# Alimentations.net
KiCad netlist of a schematic drawn in Altium Designer
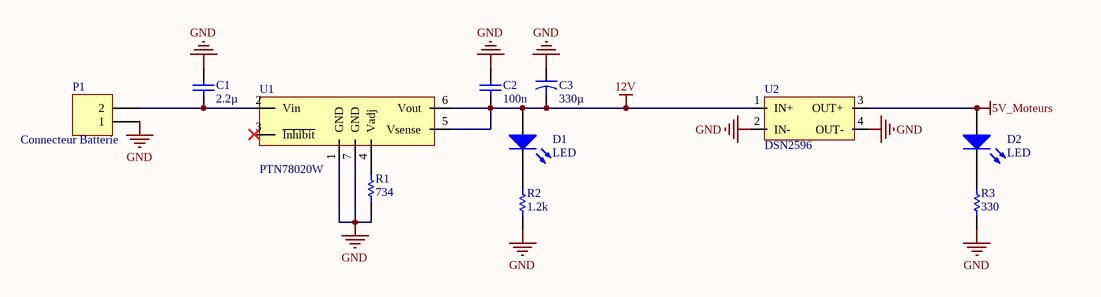
[diagram p0: Alimentations.SchDoc]

(export (version "E")
  (design (tool "Eeschema 10.0.6"))
  (components
    (comp (ref "C1")
      (value "2.2µ")
      (footprint "RAD-0.3")
      (fields (field (name "Comment") "Cap") (field (name "PUBLISHER") "Altium Limited"))
      (libsource (lib "Miscellaneous Devices") (part "Cap"))
    )
    (comp (ref "C2")
      (value "100n")
      (footprint "RAD-0.3")
      (fields (field (name "Comment") "Cap") (field (name "PUBLISHER") "Altium Limited"))
      (libsource (lib "Miscellaneous Devices") (part "Cap"))
    )
    (comp (ref "C3")
      (value "330µ")
      (footprint "CAPR5-4X5")
      (fields (field (name "Comment") "Cap2") (field (name "PUBLISHER") "Altium Limited"))
      (libsource (lib "Miscellaneous Devices") (part "Cap2"))
    )
    (comp (ref "D1")
      (value "LED")
      (footprint "C0805")
      (description "LED Bleu")
      (fields (field (name "PUBLISHER") "Altium Limited"))
      (libsource (lib "Miscellaneous Devices") (part "LED1"))
    )
    (comp (ref "D2")
      (value "LED")
      (footprint "C0805")
      (description "LED Verte")
      (fields (field (name "PUBLISHER") "Altium Limited"))
      (libsource (lib "Miscellaneous Devices") (part "LED1"))
    )
    (comp (ref "P1")
      (value "Connecteur Batterie")
      (footprint "HDR1X2")
      (description "Header, 2-Pin")
      (fields (field (name "PUBLISHER") "Altium Limited"))
      (libsource (lib "Miscellaneous Connectors") (part "Header 2"))
    )
    (comp (ref "R1")
      (value "734")
      (footprint "AXIAL-0.3")
      (description "734R 1%")
      (fields (field (name "Comment") "Res1") (field (name "PUBLISHER") "Altium Limited"))
      (libsource (lib "Miscellaneous Devices") (part "Res1"))
    )
    (comp (ref "R2")
      (value "1.2k")
      (footprint "AXIAL-0.3")
      (fields (field (name "Comment") "Res1") (field (name "PUBLISHER") "Altium Limited"))
      (libsource (lib "Miscellaneous Devices") (part "Res1"))
    )
    (comp (ref "R3")
      (value "330")
      (footprint "AXIAL-0.3")
      (description "330R")
      (fields (field (name "Comment") "Res1") (field (name "PUBLISHER") "Altium Limited"))
      (libsource (lib "Miscellaneous Devices") (part "Res1"))
    )
    (comp (ref "U1")
      (value "PTN78020W")
      (description "Alim à découpage 6A")
      (libsource (lib "lib_Gabriel") (part "PTN78020W"))
    )
    (comp (ref "U2")
      (value "DSN2596")
      (description "Module Buck 24V 12V 5V - 3A")
      (libsource (lib "lib_Gabriel") (part "DSN2596"))
    )
  )
  (nets
    (net (code "1") (name "5V_Moteurs") (class "Default")
      (node (ref "D2") (pin "1") (pinfunction "A_1") (pintype "passive"))
      (node (ref "U2") (pin "3") (pinfunction "OUT+_3") (pintype "passive"))
    )
    (net (code "2") (name "12V") (class "Default")
      (node (ref "C2") (pin "1") (pinfunction "1_1") (pintype "passive"))
      (node (ref "C3") (pin "2") (pinfunction "2_2") (pintype "passive"))
      (node (ref "D1") (pin "1") (pinfunction "A_1") (pintype "passive"))
      (node (ref "U1") (pin "5") (pinfunction "Vsense_5") (pintype "passive"))
      (node (ref "U1") (pin "6") (pinfunction "Vout_6") (pintype "passive"))
      (node (ref "U2") (pin "1") (pinfunction "IN+_1") (pintype "passive"))
    )
    (net (code "3") (name "GND") (class "Default")
      (node (ref "C1") (pin "2") (pinfunction "2_2") (pintype "passive"))
      (node (ref "C2") (pin "2") (pinfunction "2_2") (pintype "passive"))
      (node (ref "C3") (pin "1") (pinfunction "1_1") (pintype "passive"))
      (node (ref "P1") (pin "1") (pinfunction "1_1") (pintype "passive"))
      (node (ref "R1") (pin "1") (pinfunction "1_1") (pintype "passive"))
      (node (ref "R2") (pin "2") (pinfunction "2_2") (pintype "passive"))
      (node (ref "R3") (pin "2") (pinfunction "2_2") (pintype "passive"))
      (node (ref "U1") (pin "1") (pinfunction "GND_1") (pintype "passive"))
      (node (ref "U1") (pin "7") (pinfunction "GND_7") (pintype "passive"))
      (node (ref "U2") (pin "2") (pinfunction "IN-_2") (pintype "passive"))
      (node (ref "U2") (pin "4") (pinfunction "OUT-_4") (pintype "passive"))
    )
    (net (code "4") (name "Net-(D1-K)") (class "Default")
      (node (ref "D1") (pin "2") (pinfunction "K_2") (pintype "passive"))
      (node (ref "R2") (pin "1") (pinfunction "1_1") (pintype "passive"))
    )
    (net (code "5") (name "Net-(D2-K)") (class "Default")
      (node (ref "D2") (pin "2") (pinfunction "K_2") (pintype "passive"))
      (node (ref "R3") (pin "1") (pinfunction "1_1") (pintype "passive"))
    )
    (net (code "6") (name "Net-(U1-Vadj)") (class "Default")
      (node (ref "R1") (pin "2") (pinfunction "2_2") (pintype "passive"))
      (node (ref "U1") (pin "4") (pinfunction "Vadj_4") (pintype "passive"))
    )
    (net (code "7") (name "Net-(U1-Vin)") (class "Default")
      (node (ref "C1") (pin "1") (pinfunction "1_1") (pintype "passive"))
      (node (ref "P1") (pin "2") (pinfunction "2_2") (pintype "passive"))
      (node (ref "U1") (pin "2") (pinfunction "Vin_2") (pintype "passive"))
    )
    (net (code "8") (name "unconnected-(U1-Inhibit-Pad3)") (class "Default")
      (node (ref "U1") (pin "3") (pinfunction "Inhibit_3") (pintype "passive+no_connect"))
    )
  )
)
